# DAM16_Relays.net
KiCad netlist of a schematic drawn in Altium Designer
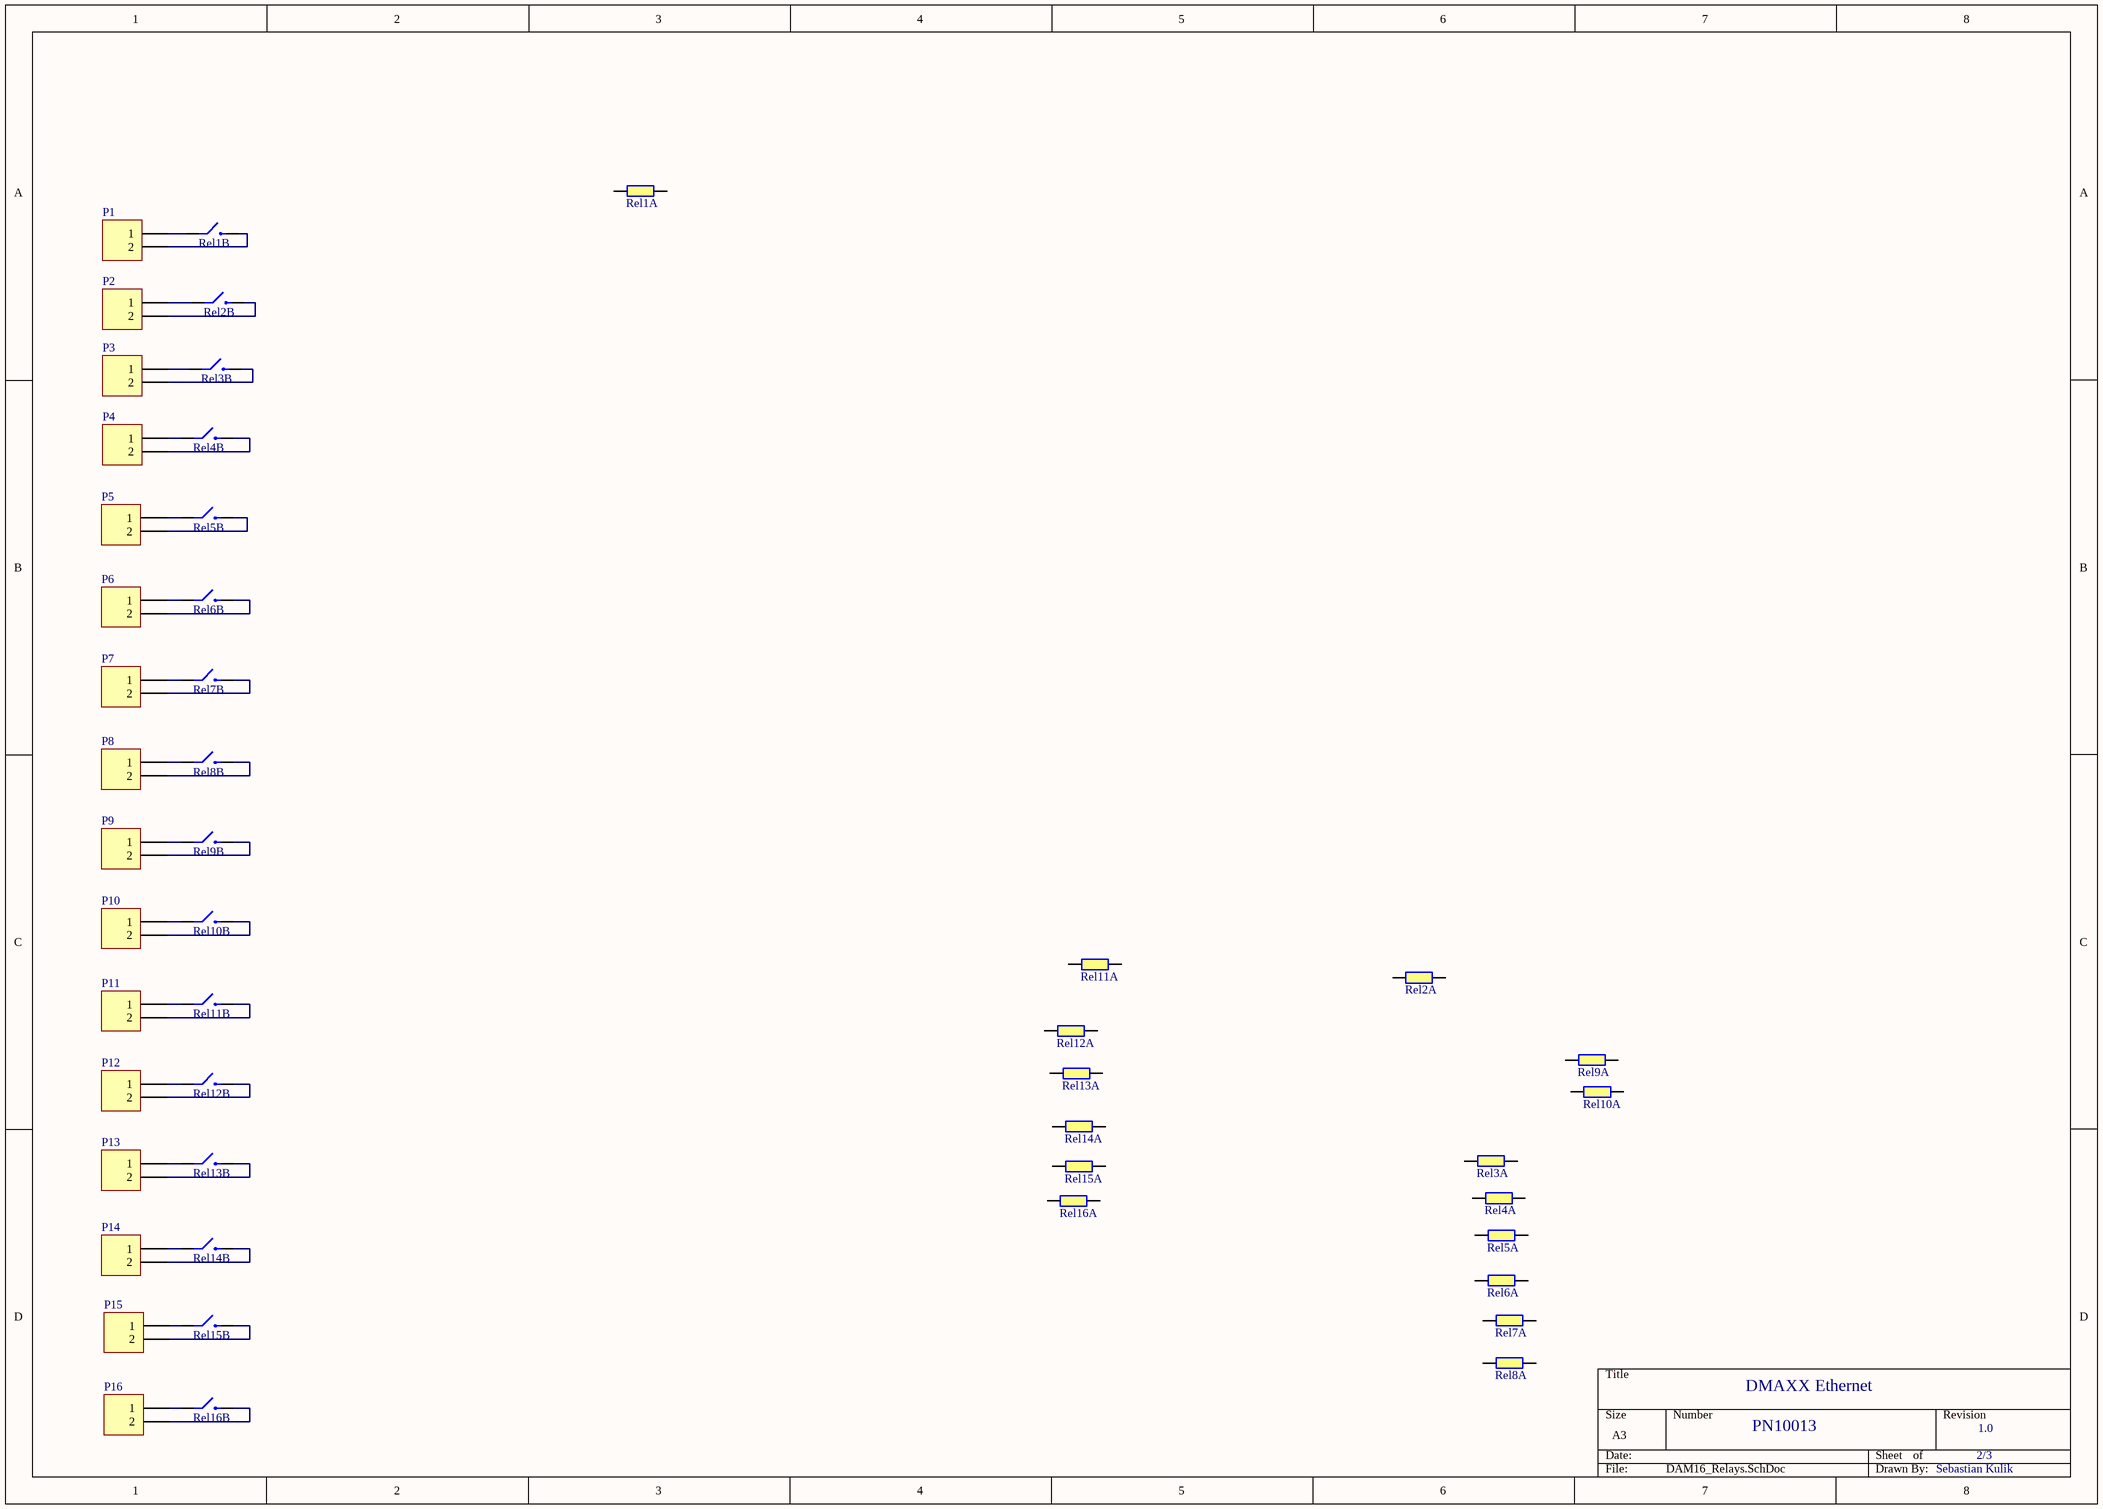
[diagram p0: DAM16_Relays.SchDoc]

(export (version "E")
  (design (tool "Eeschema 10.0.6"))
  (components
    (comp (ref "P1")
      (value "PHOENIX_1715721")
      (footprint "Phoenix-2-5_08")
      (description "Phoenix, 2 pol, 5.08mm, 22A, 715721")
      (fields (field (name "MANUFACTURER") "Phoenix") (field (name "PUBLISHER") "Sebastian Kulik"))
      (libsource (lib "Connectors") (part "2Pol_1715721"))
    )
    (comp (ref "P2")
      (value "PHOENIX_1715721")
      (footprint "Phoenix-2-5_08")
      (description "Phoenix, 2 pol, 5.08mm, 22A, 715721")
      (fields (field (name "MANUFACTURER") "Phoenix") (field (name "PUBLISHER") "Sebastian Kulik"))
      (libsource (lib "Connectors") (part "2Pol_1715721"))
    )
    (comp (ref "P3")
      (value "PHOENIX_1715721")
      (footprint "Phoenix-2-5_08")
      (description "Phoenix, 2 pol, 5.08mm, 22A, 715721")
      (fields (field (name "MANUFACTURER") "Phoenix") (field (name "PUBLISHER") "Sebastian Kulik"))
      (libsource (lib "Connectors") (part "2Pol_1715721"))
    )
    (comp (ref "P4")
      (value "PHOENIX_1715721")
      (footprint "Phoenix-2-5_08")
      (description "Phoenix, 2 pol, 5.08mm, 22A, 715721")
      (fields (field (name "MANUFACTURER") "Phoenix") (field (name "PUBLISHER") "Sebastian Kulik"))
      (libsource (lib "Connectors") (part "2Pol_1715721"))
    )
    (comp (ref "P5")
      (value "PHOENIX_1715721")
      (footprint "Phoenix-2-5_08")
      (description "Phoenix, 2 pol, 5.08mm, 22A, 715721")
      (fields (field (name "MANUFACTURER") "Phoenix") (field (name "PUBLISHER") "Sebastian Kulik"))
      (libsource (lib "Connectors") (part "2Pol_1715721"))
    )
    (comp (ref "P6")
      (value "PHOENIX_1715721")
      (footprint "Phoenix-2-5_08")
      (description "Phoenix, 2 pol, 5.08mm, 22A, 715721")
      (fields (field (name "MANUFACTURER") "Phoenix") (field (name "PUBLISHER") "Sebastian Kulik"))
      (libsource (lib "Connectors") (part "2Pol_1715721"))
    )
    (comp (ref "P7")
      (value "PHOENIX_1715721")
      (footprint "Phoenix-2-5_08")
      (description "Phoenix, 2 pol, 5.08mm, 22A, 715721")
      (fields (field (name "MANUFACTURER") "Phoenix") (field (name "PUBLISHER") "Sebastian Kulik"))
      (libsource (lib "Connectors") (part "2Pol_1715721"))
    )
    (comp (ref "P8")
      (value "PHOENIX_1715721")
      (footprint "Phoenix-2-5_08")
      (description "Phoenix, 2 pol, 5.08mm, 22A, 715721")
      (fields (field (name "MANUFACTURER") "Phoenix") (field (name "PUBLISHER") "Sebastian Kulik"))
      (libsource (lib "Connectors") (part "2Pol_1715721"))
    )
    (comp (ref "P9")
      (value "PHOENIX_1715721")
      (footprint "Phoenix-2-5_08")
      (description "Phoenix, 2 pol, 5.08mm, 22A, 715721")
      (fields (field (name "MANUFACTURER") "Phoenix") (field (name "PUBLISHER") "Sebastian Kulik"))
      (libsource (lib "Connectors") (part "2Pol_1715721"))
    )
    (comp (ref "P10")
      (value "PHOENIX_1715721")
      (footprint "Phoenix-2-5_08")
      (description "Phoenix, 2 pol, 5.08mm, 22A, 715721")
      (fields (field (name "MANUFACTURER") "Phoenix") (field (name "PUBLISHER") "Sebastian Kulik"))
      (libsource (lib "Connectors") (part "2Pol_1715721"))
    )
    (comp (ref "P11")
      (value "PHOENIX_1715721")
      (footprint "Phoenix-2-5_08")
      (description "Phoenix, 2 pol, 5.08mm, 22A, 715721")
      (fields (field (name "MANUFACTURER") "Phoenix") (field (name "PUBLISHER") "Sebastian Kulik"))
      (libsource (lib "Connectors") (part "2Pol_1715721"))
    )
    (comp (ref "P12")
      (value "PHOENIX_1715721")
      (footprint "Phoenix-2-5_08")
      (description "Phoenix, 2 pol, 5.08mm, 22A, 715721")
      (fields (field (name "MANUFACTURER") "Phoenix") (field (name "PUBLISHER") "Sebastian Kulik"))
      (libsource (lib "Connectors") (part "2Pol_1715721"))
    )
    (comp (ref "P13")
      (value "PHOENIX_1715721")
      (footprint "Phoenix-2-5_08")
      (description "Phoenix, 2 pol, 5.08mm, 22A, 715721")
      (fields (field (name "MANUFACTURER") "Phoenix") (field (name "PUBLISHER") "Sebastian Kulik"))
      (libsource (lib "Connectors") (part "2Pol_1715721"))
    )
    (comp (ref "P14")
      (value "PHOENIX_1715721")
      (footprint "Phoenix-2-5_08")
      (description "Phoenix, 2 pol, 5.08mm, 22A, 715721")
      (fields (field (name "MANUFACTURER") "Phoenix") (field (name "PUBLISHER") "Sebastian Kulik"))
      (libsource (lib "Connectors") (part "2Pol_1715721"))
    )
    (comp (ref "P15")
      (value "PHOENIX_1715721")
      (footprint "Phoenix-2-5_08")
      (description "Phoenix, 2 pol, 5.08mm, 22A, 715721")
      (fields (field (name "MANUFACTURER") "Phoenix") (field (name "PUBLISHER") "Sebastian Kulik"))
      (libsource (lib "Connectors") (part "2Pol_1715721"))
    )
    (comp (ref "P16")
      (value "PHOENIX_1715721")
      (footprint "Phoenix-2-5_08")
      (description "Phoenix, 2 pol, 5.08mm, 22A, 715721")
      (fields (field (name "MANUFACTURER") "Phoenix") (field (name "PUBLISHER") "Sebastian Kulik"))
      (libsource (lib "Connectors") (part "2Pol_1715721"))
    )
    (comp (ref "Rel1")
      (value "Omron_G5RL-1A-E-HR")
      (footprint "Omron-G5RL-HR")
      (description "Omron_G5RL-1A-E-HR, 16A, 12V, 400mW")
      (fields (field (name "MANUFACTURER") "Finder") (field (name "PUBLISHER") "Sebastian Kulik"))
      (libsource (lib "Mechanical") (part "Omron_G5RL-1A-E-HR"))
    )
    (comp (ref "Rel2")
      (value "Omron_G5RL-1A-E-HR")
      (footprint "Omron-G5RL-HR")
      (description "Omron_G5RL-1A-E-HR, 16A, 12V, 400mW")
      (fields (field (name "MANUFACTURER") "Finder") (field (name "PUBLISHER") "Sebastian Kulik"))
      (libsource (lib "Mechanical") (part "Omron_G5RL-1A-E-HR"))
    )
    (comp (ref "Rel3")
      (value "Omron_G5RL-1A-E-HR")
      (footprint "Omron-G5RL-HR")
      (description "Omron_G5RL-1A-E-HR, 16A, 12V, 400mW")
      (fields (field (name "MANUFACTURER") "Finder") (field (name "PUBLISHER") "Sebastian Kulik"))
      (libsource (lib "Mechanical") (part "Omron_G5RL-1A-E-HR"))
    )
    (comp (ref "Rel4")
      (value "Omron_G5RL-1A-E-HR")
      (footprint "Omron-G5RL-HR")
      (description "Omron_G5RL-1A-E-HR, 16A, 12V, 400mW")
      (fields (field (name "MANUFACTURER") "Finder") (field (name "PUBLISHER") "Sebastian Kulik"))
      (libsource (lib "Mechanical") (part "Omron_G5RL-1A-E-HR"))
    )
    (comp (ref "Rel5")
      (value "Omron_G5RL-1A-E-HR")
      (footprint "Omron-G5RL-HR")
      (description "Omron_G5RL-1A-E-HR, 16A, 12V, 400mW")
      (fields (field (name "MANUFACTURER") "Finder") (field (name "PUBLISHER") "Sebastian Kulik"))
      (libsource (lib "Mechanical") (part "Omron_G5RL-1A-E-HR"))
    )
    (comp (ref "Rel6")
      (value "Omron_G5RL-1A-E-HR")
      (footprint "Omron-G5RL-HR")
      (description "Omron_G5RL-1A-E-HR, 16A, 12V, 400mW")
      (fields (field (name "MANUFACTURER") "Finder") (field (name "PUBLISHER") "Sebastian Kulik"))
      (libsource (lib "Mechanical") (part "Omron_G5RL-1A-E-HR"))
    )
    (comp (ref "Rel7")
      (value "Omron_G5RL-1A-E-HR")
      (footprint "Omron-G5RL-HR")
      (description "Omron_G5RL-1A-E-HR, 16A, 12V, 400mW")
      (fields (field (name "MANUFACTURER") "Finder") (field (name "PUBLISHER") "Sebastian Kulik"))
      (libsource (lib "Mechanical") (part "Omron_G5RL-1A-E-HR"))
    )
    (comp (ref "Rel8")
      (value "Omron_G5RL-1A-E-HR")
      (footprint "Omron-G5RL-HR")
      (description "Omron_G5RL-1A-E-HR, 16A, 12V, 400mW")
      (fields (field (name "MANUFACTURER") "Finder") (field (name "PUBLISHER") "Sebastian Kulik"))
      (libsource (lib "Mechanical") (part "Omron_G5RL-1A-E-HR"))
    )
    (comp (ref "Rel9")
      (value "Omron_G5RL-1A-E-HR")
      (footprint "Omron-G5RL-HR")
      (description "Omron_G5RL-1A-E-HR, 16A, 12V, 400mW")
      (fields (field (name "MANUFACTURER") "Finder") (field (name "PUBLISHER") "Sebastian Kulik"))
      (libsource (lib "Mechanical") (part "Omron_G5RL-1A-E-HR"))
    )
    (comp (ref "Rel10")
      (value "Omron_G5RL-1A-E-HR")
      (footprint "Omron-G5RL-HR")
      (description "Omron_G5RL-1A-E-HR, 16A, 12V, 400mW")
      (fields (field (name "MANUFACTURER") "Finder") (field (name "PUBLISHER") "Sebastian Kulik"))
      (libsource (lib "Mechanical") (part "Omron_G5RL-1A-E-HR"))
    )
    (comp (ref "Rel11")
      (value "Omron_G5RL-1A-E-HR")
      (footprint "Omron-G5RL-HR")
      (description "Omron_G5RL-1A-E-HR, 16A, 12V, 400mW")
      (fields (field (name "MANUFACTURER") "Finder") (field (name "PUBLISHER") "Sebastian Kulik"))
      (libsource (lib "Mechanical") (part "Omron_G5RL-1A-E-HR"))
    )
    (comp (ref "Rel12")
      (value "Omron_G5RL-1A-E-HR")
      (footprint "Omron-G5RL-HR")
      (description "Omron_G5RL-1A-E-HR, 16A, 12V, 400mW")
      (fields (field (name "MANUFACTURER") "Finder") (field (name "PUBLISHER") "Sebastian Kulik"))
      (libsource (lib "Mechanical") (part "Omron_G5RL-1A-E-HR"))
    )
    (comp (ref "Rel13")
      (value "Omron_G5RL-1A-E-HR")
      (footprint "Omron-G5RL-HR")
      (description "Omron_G5RL-1A-E-HR, 16A, 12V, 400mW")
      (fields (field (name "MANUFACTURER") "Finder") (field (name "PUBLISHER") "Sebastian Kulik"))
      (libsource (lib "Mechanical") (part "Omron_G5RL-1A-E-HR"))
    )
    (comp (ref "Rel14")
      (value "Omron_G5RL-1A-E-HR")
      (footprint "Omron-G5RL-HR")
      (description "Omron_G5RL-1A-E-HR, 16A, 12V, 400mW")
      (fields (field (name "MANUFACTURER") "Finder") (field (name "PUBLISHER") "Sebastian Kulik"))
      (libsource (lib "Mechanical") (part "Omron_G5RL-1A-E-HR"))
    )
    (comp (ref "Rel15")
      (value "Omron_G5RL-1A-E-HR")
      (footprint "Omron-G5RL-HR")
      (description "Omron_G5RL-1A-E-HR, 16A, 12V, 400mW")
      (fields (field (name "MANUFACTURER") "Finder") (field (name "PUBLISHER") "Sebastian Kulik"))
      (libsource (lib "Mechanical") (part "Omron_G5RL-1A-E-HR"))
    )
    (comp (ref "Rel16")
      (value "Omron_G5RL-1A-E-HR")
      (footprint "Omron-G5RL-HR")
      (description "Omron_G5RL-1A-E-HR, 16A, 12V, 400mW")
      (fields (field (name "MANUFACTURER") "Finder") (field (name "PUBLISHER") "Sebastian Kulik"))
      (libsource (lib "Mechanical") (part "Omron_G5RL-1A-E-HR"))
    )
  )
  (nets
    (net (code "1") (name "Net-(P1-Pad1)") (class "Default")
      (node (ref "P1") (pin "1") (pinfunction "1_1") (pintype "passive"))
      (node (ref "Rel1") (pin "3") (pinfunction "3_3") (pintype "passive"))
    )
    (net (code "2") (name "Net-(P1-Pad2)") (class "Default")
      (node (ref "P1") (pin "2") (pinfunction "2_2") (pintype "passive"))
      (node (ref "Rel1") (pin "4") (pinfunction "4_4") (pintype "passive"))
    )
    (net (code "3") (name "Net-(P2-Pad1)") (class "Default")
      (node (ref "P2") (pin "1") (pinfunction "1_1") (pintype "passive"))
      (node (ref "Rel2") (pin "3") (pinfunction "3_3") (pintype "passive"))
    )
    (net (code "4") (name "Net-(P2-Pad2)") (class "Default")
      (node (ref "P2") (pin "2") (pinfunction "2_2") (pintype "passive"))
      (node (ref "Rel2") (pin "4") (pinfunction "4_4") (pintype "passive"))
    )
    (net (code "5") (name "Net-(P3-Pad1)") (class "Default")
      (node (ref "P3") (pin "1") (pinfunction "1_1") (pintype "passive"))
      (node (ref "Rel3") (pin "3") (pinfunction "3_3") (pintype "passive"))
    )
    (net (code "6") (name "Net-(P3-Pad2)") (class "Default")
      (node (ref "P3") (pin "2") (pinfunction "2_2") (pintype "passive"))
      (node (ref "Rel3") (pin "4") (pinfunction "4_4") (pintype "passive"))
    )
    (net (code "7") (name "Net-(P4-Pad1)") (class "Default")
      (node (ref "P4") (pin "1") (pinfunction "1_1") (pintype "passive"))
      (node (ref "Rel4") (pin "3") (pinfunction "3_3") (pintype "passive"))
    )
    (net (code "8") (name "Net-(P4-Pad2)") (class "Default")
      (node (ref "P4") (pin "2") (pinfunction "2_2") (pintype "passive"))
      (node (ref "Rel4") (pin "4") (pinfunction "4_4") (pintype "passive"))
    )
    (net (code "9") (name "Net-(P5-Pad1)") (class "Default")
      (node (ref "P5") (pin "1") (pinfunction "1_1") (pintype "passive"))
      (node (ref "Rel5") (pin "3") (pinfunction "3_3") (pintype "passive"))
    )
    (net (code "10") (name "Net-(P5-Pad2)") (class "Default")
      (node (ref "P5") (pin "2") (pinfunction "2_2") (pintype "passive"))
      (node (ref "Rel5") (pin "4") (pinfunction "4_4") (pintype "passive"))
    )
    (net (code "11") (name "Net-(P6-Pad1)") (class "Default")
      (node (ref "P6") (pin "1") (pinfunction "1_1") (pintype "passive"))
      (node (ref "Rel6") (pin "3") (pinfunction "3_3") (pintype "passive"))
    )
    (net (code "12") (name "Net-(P6-Pad2)") (class "Default")
      (node (ref "P6") (pin "2") (pinfunction "2_2") (pintype "passive"))
      (node (ref "Rel6") (pin "4") (pinfunction "4_4") (pintype "passive"))
    )
    (net (code "13") (name "Net-(P7-Pad1)") (class "Default")
      (node (ref "P7") (pin "1") (pinfunction "1_1") (pintype "passive"))
      (node (ref "Rel7") (pin "3") (pinfunction "3_3") (pintype "passive"))
    )
    (net (code "14") (name "Net-(P7-Pad2)") (class "Default")
      (node (ref "P7") (pin "2") (pinfunction "2_2") (pintype "passive"))
      (node (ref "Rel7") (pin "4") (pinfunction "4_4") (pintype "passive"))
    )
    (net (code "15") (name "Net-(P8-Pad1)") (class "Default")
      (node (ref "P8") (pin "1") (pinfunction "1_1") (pintype "passive"))
      (node (ref "Rel8") (pin "3") (pinfunction "3_3") (pintype "passive"))
    )
    (net (code "16") (name "Net-(P8-Pad2)") (class "Default")
      (node (ref "P8") (pin "2") (pinfunction "2_2") (pintype "passive"))
      (node (ref "Rel8") (pin "4") (pinfunction "4_4") (pintype "passive"))
    )
    (net (code "17") (name "Net-(P9-Pad1)") (class "Default")
      (node (ref "P9") (pin "1") (pinfunction "1_1") (pintype "passive"))
      (node (ref "Rel9") (pin "3") (pinfunction "3_3") (pintype "passive"))
    )
    (net (code "18") (name "Net-(P9-Pad2)") (class "Default")
      (node (ref "P9") (pin "2") (pinfunction "2_2") (pintype "passive"))
      (node (ref "Rel9") (pin "4") (pinfunction "4_4") (pintype "passive"))
    )
    (net (code "19") (name "Net-(P10-Pad1)") (class "Default")
      (node (ref "P10") (pin "1") (pinfunction "1_1") (pintype "passive"))
      (node (ref "Rel10") (pin "3") (pinfunction "3_3") (pintype "passive"))
    )
    (net (code "20") (name "Net-(P10-Pad2)") (class "Default")
      (node (ref "P10") (pin "2") (pinfunction "2_2") (pintype "passive"))
      (node (ref "Rel10") (pin "4") (pinfunction "4_4") (pintype "passive"))
    )
    (net (code "21") (name "Net-(P11-Pad1)") (class "Default")
      (node (ref "P11") (pin "1") (pinfunction "1_1") (pintype "passive"))
      (node (ref "Rel11") (pin "3") (pinfunction "3_3") (pintype "passive"))
    )
    (net (code "22") (name "Net-(P11-Pad2)") (class "Default")
      (node (ref "P11") (pin "2") (pinfunction "2_2") (pintype "passive"))
      (node (ref "Rel11") (pin "4") (pinfunction "4_4") (pintype "passive"))
    )
    (net (code "23") (name "Net-(P12-Pad1)") (class "Default")
      (node (ref "P12") (pin "1") (pinfunction "1_1") (pintype "passive"))
      (node (ref "Rel12") (pin "3") (pinfunction "3_3") (pintype "passive"))
    )
    (net (code "24") (name "Net-(P12-Pad2)") (class "Default")
      (node (ref "P12") (pin "2") (pinfunction "2_2") (pintype "passive"))
      (node (ref "Rel12") (pin "4") (pinfunction "4_4") (pintype "passive"))
    )
    (net (code "25") (name "Net-(P13-Pad1)") (class "Default")
      (node (ref "P13") (pin "1") (pinfunction "1_1") (pintype "passive"))
      (node (ref "Rel13") (pin "3") (pinfunction "3_3") (pintype "passive"))
    )
    (net (code "26") (name "Net-(P13-Pad2)") (class "Default")
      (node (ref "P13") (pin "2") (pinfunction "2_2") (pintype "passive"))
      (node (ref "Rel13") (pin "4") (pinfunction "4_4") (pintype "passive"))
    )
    (net (code "27") (name "Net-(P14-Pad1)") (class "Default")
      (node (ref "P14") (pin "1") (pinfunction "1_1") (pintype "passive"))
      (node (ref "Rel14") (pin "3") (pinfunction "3_3") (pintype "passive"))
    )
    (net (code "28") (name "Net-(P14-Pad2)") (class "Default")
      (node (ref "P14") (pin "2") (pinfunction "2_2") (pintype "passive"))
      (node (ref "Rel14") (pin "4") (pinfunction "4_4") (pintype "passive"))
    )
    (net (code "29") (name "Net-(P15-Pad1)") (class "Default")
      (node (ref "P15") (pin "1") (pinfunction "1_1") (pintype "passive"))
      (node (ref "Rel15") (pin "3") (pinfunction "3_3") (pintype "passive"))
    )
    (net (code "30") (name "Net-(P15-Pad2)") (class "Default")
      (node (ref "P15") (pin "2") (pinfunction "2_2") (pintype "passive"))
      (node (ref "Rel15") (pin "4") (pinfunction "4_4") (pintype "passive"))
    )
    (net (code "31") (name "Net-(P16-Pad1)") (class "Default")
      (node (ref "P16") (pin "1") (pinfunction "1_1") (pintype "passive"))
      (node (ref "Rel16") (pin "3") (pinfunction "3_3") (pintype "passive"))
    )
    (net (code "32") (name "Net-(P16-Pad2)") (class "Default")
      (node (ref "P16") (pin "2") (pinfunction "2_2") (pintype "passive"))
      (node (ref "Rel16") (pin "4") (pinfunction "4_4") (pintype "passive"))
    )
    (net (code "33") (name "unconnected-(Rel1-Pad1)") (class "Default")
      (node (ref "Rel1") (pin "1") (pinfunction "1_1") (pintype "passive"))
    )
    (net (code "34") (name "unconnected-(Rel1-Pad2)") (class "Default")
      (node (ref "Rel1") (pin "2") (pinfunction "2_2") (pintype "passive"))
    )
    (net (code "35") (name "unconnected-(Rel2-Pad1)") (class "Default")
      (node (ref "Rel2") (pin "1") (pinfunction "1_1") (pintype "passive"))
    )
    (net (code "36") (name "unconnected-(Rel2-Pad2)") (class "Default")
      (node (ref "Rel2") (pin "2") (pinfunction "2_2") (pintype "passive"))
    )
    (net (code "37") (name "unconnected-(Rel3-Pad1)") (class "Default")
      (node (ref "Rel3") (pin "1") (pinfunction "1_1") (pintype "passive"))
    )
    (net (code "38") (name "unconnected-(Rel3-Pad2)") (class "Default")
      (node (ref "Rel3") (pin "2") (pinfunction "2_2") (pintype "passive"))
    )
    (net (code "39") (name "unconnected-(Rel4-Pad1)") (class "Default")
      (node (ref "Rel4") (pin "1") (pinfunction "1_1") (pintype "passive"))
    )
    (net (code "40") (name "unconnected-(Rel4-Pad2)") (class "Default")
      (node (ref "Rel4") (pin "2") (pinfunction "2_2") (pintype "passive"))
    )
    (net (code "41") (name "unconnected-(Rel5-Pad1)") (class "Default")
      (node (ref "Rel5") (pin "1") (pinfunction "1_1") (pintype "passive"))
    )
    (net (code "42") (name "unconnected-(Rel5-Pad2)") (class "Default")
      (node (ref "Rel5") (pin "2") (pinfunction "2_2") (pintype "passive"))
    )
    (net (code "43") (name "unconnected-(Rel6-Pad1)") (class "Default")
      (node (ref "Rel6") (pin "1") (pinfunction "1_1") (pintype "passive"))
    )
    (net (code "44") (name "unconnected-(Rel6-Pad2)") (class "Default")
      (node (ref "Rel6") (pin "2") (pinfunction "2_2") (pintype "passive"))
    )
    (net (code "45") (name "unconnected-(Rel7-Pad1)") (class "Default")
      (node (ref "Rel7") (pin "1") (pinfunction "1_1") (pintype "passive"))
    )
    (net (code "46") (name "unconnected-(Rel7-Pad2)") (class "Default")
      (node (ref "Rel7") (pin "2") (pinfunction "2_2") (pintype "passive"))
    )
    (net (code "47") (name "unconnected-(Rel8-Pad1)") (class "Default")
      (node (ref "Rel8") (pin "1") (pinfunction "1_1") (pintype "passive"))
    )
    (net (code "48") (name "unconnected-(Rel8-Pad2)") (class "Default")
      (node (ref "Rel8") (pin "2") (pinfunction "2_2") (pintype "passive"))
    )
    (net (code "49") (name "unconnected-(Rel9-Pad1)") (class "Default")
      (node (ref "Rel9") (pin "1") (pinfunction "1_1") (pintype "passive"))
    )
    (net (code "50") (name "unconnected-(Rel9-Pad2)") (class "Default")
      (node (ref "Rel9") (pin "2") (pinfunction "2_2") (pintype "passive"))
    )
    (net (code "51") (name "unconnected-(Rel10-Pad1)") (class "Default")
      (node (ref "Rel10") (pin "1") (pinfunction "1_1") (pintype "passive"))
    )
    (net (code "52") (name "unconnected-(Rel10-Pad2)") (class "Default")
      (node (ref "Rel10") (pin "2") (pinfunction "2_2") (pintype "passive"))
    )
    (net (code "53") (name "unconnected-(Rel11-Pad1)") (class "Default")
      (node (ref "Rel11") (pin "1") (pinfunction "1_1") (pintype "passive"))
    )
    (net (code "54") (name "unconnected-(Rel11-Pad2)") (class "Default")
      (node (ref "Rel11") (pin "2") (pinfunction "2_2") (pintype "passive"))
    )
    (net (code "55") (name "unconnected-(Rel12-Pad1)") (class "Default")
      (node (ref "Rel12") (pin "1") (pinfunction "1_1") (pintype "passive"))
    )
    (net (code "56") (name "unconnected-(Rel12-Pad2)") (class "Default")
      (node (ref "Rel12") (pin "2") (pinfunction "2_2") (pintype "passive"))
    )
    (net (code "57") (name "unconnected-(Rel13-Pad1)") (class "Default")
      (node (ref "Rel13") (pin "1") (pinfunction "1_1") (pintype "passive"))
    )
    (net (code "58") (name "unconnected-(Rel13-Pad2)") (class "Default")
      (node (ref "Rel13") (pin "2") (pinfunction "2_2") (pintype "passive"))
    )
    (net (code "59") (name "unconnected-(Rel14-Pad1)") (class "Default")
      (node (ref "Rel14") (pin "1") (pinfunction "1_1") (pintype "passive"))
    )
    (net (code "60") (name "unconnected-(Rel14-Pad2)") (class "Default")
      (node (ref "Rel14") (pin "2") (pinfunction "2_2") (pintype "passive"))
    )
    (net (code "61") (name "unconnected-(Rel15-Pad1)") (class "Default")
      (node (ref "Rel15") (pin "1") (pinfunction "1_1") (pintype "passive"))
    )
    (net (code "62") (name "unconnected-(Rel15-Pad2)") (class "Default")
      (node (ref "Rel15") (pin "2") (pinfunction "2_2") (pintype "passive"))
    )
    (net (code "63") (name "unconnected-(Rel16-Pad1)") (class "Default")
      (node (ref "Rel16") (pin "1") (pinfunction "1_1") (pintype "passive"))
    )
    (net (code "64") (name "unconnected-(Rel16-Pad2)") (class "Default")
      (node (ref "Rel16") (pin "2") (pinfunction "2_2") (pintype "passive"))
    )
  )
)
